# Sensor_Board.net
KiCad netlist of a schematic drawn in Altium Designer
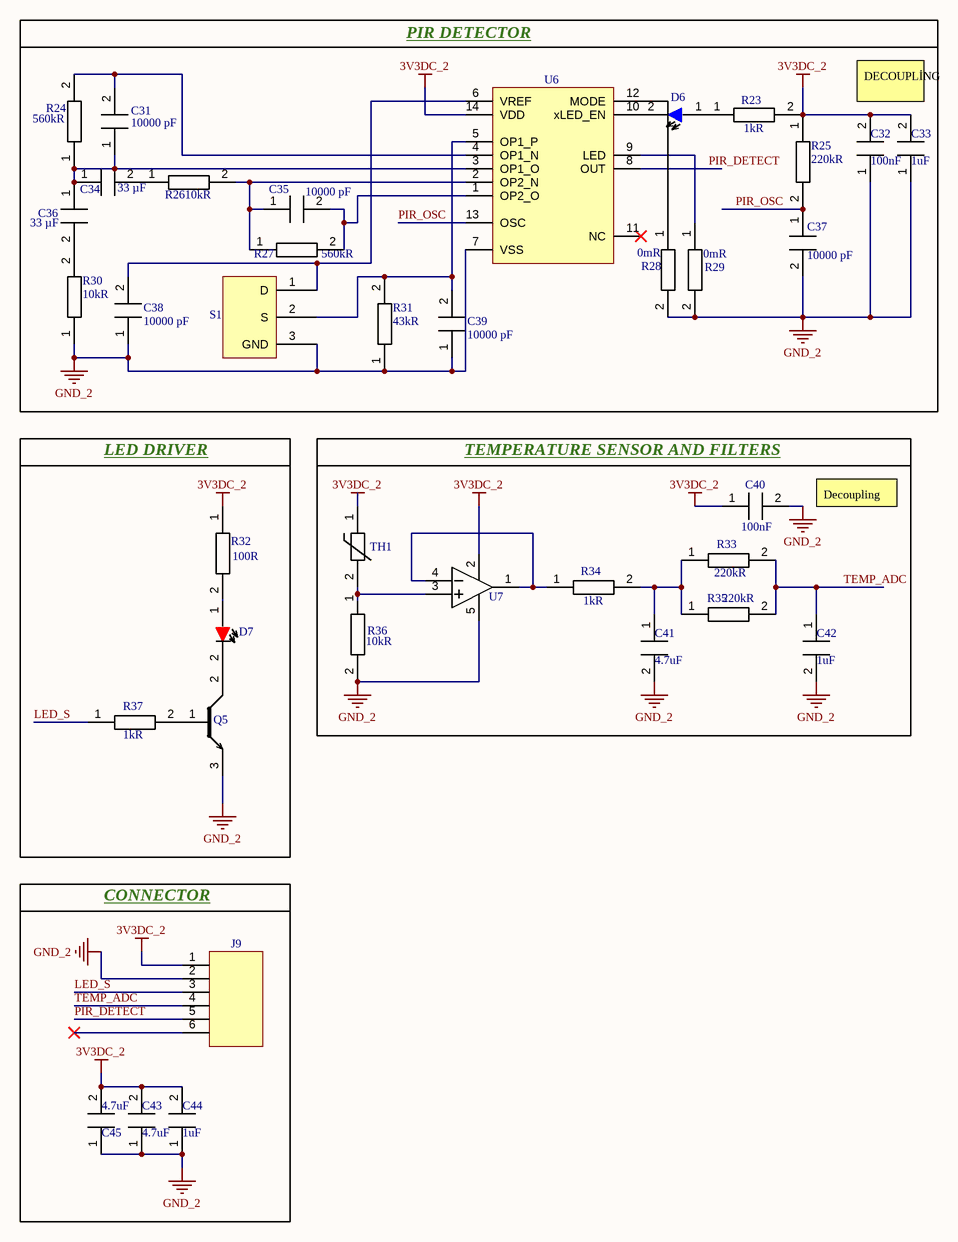
[diagram p0: Sensor_Board.SchDoc]

(export (version "E")
  (design (tool "Eeschema 10.0.6"))
  (components
    (comp (ref "C31")
      (value "10000 pF")
      (footprint "CAP_0603")
      (description "Multilayer Ceramic Capacitor, 0.01 F, 10%, X7R, 16 V, 0603 [1608 Metric] RoHS Compliant: Yes")
      (fields
        (field (name "MANUFACTURER") "Walsin Technologies")
        (field (name "MANUFACTURER PART NUMBER") "0603B103K160CT")
        (field (name "DESIGNED BY") "Ahmet Can")
      )
      (libsource (lib "AHMET_CAN_KARACAN") (part "CAP CER 10nF 0603"))
    )
    (comp (ref "C32")
      (value "CL21B104KBCNNNC")
      (footprint "CAP_0805")
      (description "Multilayer Ceramic Capacitor, 0.1 uF, 50 V, ± 10%, X7R, 0805 [2012 Metric]")
      (fields
        (field (name "MANUFACTURER") "Samsung")
        (field (name "TOLERANCE") "10%")
        (field (name "CAPACITANCE") "100nF")
      )
      (libsource (lib "AHMET_CAN_KARACAN") (part "CAP CER 100nF 0805"))
    )
    (comp (ref "C33")
      (value "1uF")
      (footprint "CAP_0805")
      (description "CAP CER %10 1uF 0805")
      (fields
        (field (name "MANUFACTURER") "Samsung")
        (field (name "MANUFACTURER PART NUMBER") "CL21B105KBFNNNE")
        (field (name "DESIGNED BY") "Ahmet Can")
      )
      (libsource (lib "AHMET_CAN_KARACAN") (part "CAP CER 1uF 0805"))
    )
    (comp (ref "C34")
      (value "33 µF")
      (footprint "CAP_1206")
      (description "Multilayer Ceramic Capacitor, 33 uF, 25 V, ± 20%, X5R, 1206 [3216 Metric]")
      (fields
        (field (name "MANUFACTURER") "TDK")
        (field (name "MANUFACTURER PART NUMBER") "C3216X5R1E336M160AC")
        (field (name "DESIGNED BY") "Ahmet Can")
      )
      (libsource (lib "AHMET_CAN_KARACAN") (part "CAP CER 33uF 1206"))
    )
    (comp (ref "C35")
      (value "10000 pF")
      (footprint "CAP_0603")
      (description "Multilayer Ceramic Capacitor, 0.01 F, 10%, X7R, 16 V, 0603 [1608 Metric] RoHS Compliant: Yes")
      (fields
        (field (name "MANUFACTURER") "Walsin Technologies")
        (field (name "MANUFACTURER PART NUMBER") "0603B103K160CT")
        (field (name "DESIGNED BY") "Ahmet Can")
      )
      (libsource (lib "AHMET_CAN_KARACAN") (part "CAP CER 10nF 0603"))
    )
    (comp (ref "C36")
      (value "33 µF")
      (footprint "CAP_1206")
      (description "Multilayer Ceramic Capacitor, 33 uF, 25 V, ± 20%, X5R, 1206 [3216 Metric]")
      (fields
        (field (name "MANUFACTURER") "TDK")
        (field (name "MANUFACTURER PART NUMBER") "C3216X5R1E336M160AC")
        (field (name "DESIGNED BY") "Ahmet Can")
      )
      (libsource (lib "AHMET_CAN_KARACAN") (part "CAP CER 33uF 1206"))
    )
    (comp (ref "C37")
      (value "10000 pF")
      (footprint "CAP_0603")
      (description "Multilayer Ceramic Capacitor, 0.01 F, 10%, X7R, 16 V, 0603 [1608 Metric] RoHS Compliant: Yes")
      (fields
        (field (name "MANUFACTURER") "Walsin Technologies")
        (field (name "MANUFACTURER PART NUMBER") "0603B103K160CT")
        (field (name "DESIGNED BY") "Ahmet Can")
      )
      (libsource (lib "AHMET_CAN_KARACAN") (part "CAP CER 10nF 0603"))
    )
    (comp (ref "C38")
      (value "10000 pF")
      (footprint "CAP_0603")
      (description "Multilayer Ceramic Capacitor, 0.01 F, 10%, X7R, 16 V, 0603 [1608 Metric] RoHS Compliant: Yes")
      (fields
        (field (name "MANUFACTURER") "Walsin Technologies")
        (field (name "MANUFACTURER PART NUMBER") "0603B103K160CT")
        (field (name "DESIGNED BY") "Ahmet Can")
      )
      (libsource (lib "AHMET_CAN_KARACAN") (part "CAP CER 10nF 0603"))
    )
    (comp (ref "C39")
      (value "10000 pF")
      (footprint "CAP_0603")
      (description "Multilayer Ceramic Capacitor, 0.01 F, 10%, X7R, 16 V, 0603 [1608 Metric] RoHS Compliant: Yes")
      (fields
        (field (name "MANUFACTURER") "Walsin Technologies")
        (field (name "MANUFACTURER PART NUMBER") "0603B103K160CT")
        (field (name "DESIGNED BY") "Ahmet Can")
      )
      (libsource (lib "AHMET_CAN_KARACAN") (part "CAP CER 10nF 0603"))
    )
    (comp (ref "C40")
      (value "CL21B104KBCNNNC")
      (footprint "CAP_0805")
      (description "Multilayer Ceramic Capacitor, 0.1 uF, 50 V, ± 10%, X7R, 0805 [2012 Metric]")
      (fields
        (field (name "MANUFACTURER") "Samsung")
        (field (name "TOLERANCE") "10%")
        (field (name "CAPACITANCE") "100nF")
      )
      (libsource (lib "AHMET_CAN_KARACAN") (part "CAP CER 100nF 0805"))
    )
    (comp (ref "C41")
      (value "4.7uF")
      (footprint "CAP_0805")
      (description "Multilayer Ceramic Capacitor, 4.7 uF, 25 V, ± 10%, X5R, 0805 [2012 Metric]")
      (fields
        (field (name "MANUFACTURER") "Samsung")
        (field (name "MANUFACTURER PART NUMBER") "CL21A475KAQNNNE")
        (field (name "DESIGNED BY") "Ahmet Can")
      )
      (libsource (lib "AHMET_CAN_KARACAN") (part "CAP CER 4.7uF 0805"))
    )
    (comp (ref "C42")
      (value "1uF")
      (footprint "CAP_0805")
      (description "CAP CER %10 1uF 0805")
      (fields
        (field (name "MANUFACTURER") "Samsung")
        (field (name "MANUFACTURER PART NUMBER") "CL21B105KBFNNNE")
      )
      (libsource (lib "AHMET_CAN_KARACAN") (part "CAP CER 1uF 0805"))
    )
    (comp (ref "C43")
      (value "4.7uF")
      (footprint "CAP_0805")
      (description "Multilayer Ceramic Capacitor, 4.7 uF, 25 V, ± 10%, X5R, 0805 [2012 Metric]")
      (fields
        (field (name "MANUFACTURER") "Samsung")
        (field (name "MANUFACTURER PART NUMBER") "CL21A475KAQNNNE")
        (field (name "DESIGNED BY") "Ahmet Can")
      )
      (libsource (lib "AHMET_CAN_KARACAN") (part "CAP CER 4.7uF 0805"))
    )
    (comp (ref "C44")
      (value "1uF")
      (footprint "CAP_0805")
      (description "CAP CER %10 1uF 0805")
      (fields
        (field (name "MANUFACTURER") "Samsung")
        (field (name "MANUFACTURER PART NUMBER") "CL21B105KBFNNNE")
        (field (name "DESIGNED BY") "Ahmet Can")
      )
      (libsource (lib "AHMET_CAN_KARACAN") (part "CAP CER 1uF 0805"))
    )
    (comp (ref "C45")
      (value "4.7uF")
      (footprint "CAP_0805")
      (description "Multilayer Ceramic Capacitor, 4.7 uF, 25 V, ± 10%, X5R, 0805 [2012 Metric]")
      (fields
        (field (name "MANUFACTURER") "Samsung")
        (field (name "MANUFACTURER PART NUMBER") "CL21A475KAQNNNE")
        (field (name "DESIGNED BY") "Ahmet Can")
      )
      (libsource (lib "AHMET_CAN_KARACAN") (part "CAP CER 4.7uF 0805"))
    )
    (comp (ref "D6")
      (value "0805BBD8100S01")
      (footprint "LED_BLUE_0805")
      (description "Blue 467nm LED Indication - Discrete 2.6V 0805 (2012 Metric)")
      (fields (field (name "MANUFACTURER") "BNDLIGHT") (field (name "DESIGNED BY") "Ahmet Can"))
      (libsource (lib "AHMET_CAN_KARACAN") (part "LED_BLUE 0805"))
    )
    (comp (ref "D7")
      (value "HSMC-C170")
      (footprint "LED_RED_0805")
      (description "Red 626nm LED Indication - Discrete 1.9V 0805 (2012 Metric)")
      (fields (field (name "MANUFACTURER") "Broadcom Avago") (field (name "DESIGNED BY") "Ahmet Can"))
      (libsource (lib "AHMET_CAN_KARACAN") (part "LED_RED 0805"))
    )
    (comp (ref "J9")
      (value "64800611622")
      (footprint "6 HOLE CONNECTOR")
      (description "WR-WTB Wire-to-Board Connectors 1.50 mm")
      (fields (field (name "MANUFACTURER") "Wurth Electronics") (field (name "DESIGNED BY") "Ahmet Can"))
      (libsource (lib "AHMET_CAN_KARACAN") (part "J_64800611622"))
    )
    (comp (ref "Q5")
      (value "MMBT3904-7-F")
      (footprint "SOT_23_3")
      (description "Transistor General Purpose BJT NPN 40 Volt 0.2A Automotive 3-Pin SOT-23-3")
      (fields (field (name "MANUFACTURER") "Diodes Zetex") (field (name "DESIGNED BY") "Ahmet Can"))
      (libsource (lib "AHMET_CAN_KARACAN") (part "Q_MMBT3904-7-F"))
    )
    (comp (ref "R23")
      (value "1kR")
      (footprint "RE_0603")
      (description "SMD Chip Resistor, 1 kOhm, ± 1%, 63 mW, 0402 [1005 Metric], Thick Film, General Purpose")
      (fields
        (field (name "MANUFACTURER") "Yageo")
        (field (name "MANUFACTURER PART NUMBER") "RC0402FR-071KL")
        (field (name "DESIGNED BY") "Ahmet Can")
      )
      (libsource (lib "AHMET_CAN_KARACAN") (part "RES 1K 0603"))
    )
    (comp (ref "R24")
      (value "560kR")
      (footprint "RE_0603")
      (description "SMD Chip Resistor, 560 kOhm, ± 5%, 100 mW, 0603 [1608 Metric], Thick Film, General Purpose")
      (fields
        (field (name "MANUFACTURER") "Yageo")
        (field (name "MANUFACTURER PART NUMBER") "RC0603JR-07560KL")
        (field (name "DESIGNED BY") "Ahmet Can")
      )
      (libsource (lib "AHMET_CAN_KARACAN") (part "RES 560K 0603"))
    )
    (comp (ref "R25")
      (value "220kR")
      (footprint "RE_0603")
      (description "SMD Chip Resistor, 220 kOhm, ± 5%, 100 mW, 0603 [1608 Metric], Thick Film, General Purpose")
      (fields
        (field (name "MANUFACTURER") "Yageo")
        (field (name "MANUFACTURER PART NUMBER") "RC0603JR-07220KL")
        (field (name "DESIGNED BY") "Ahmet Can")
      )
      (libsource (lib "AHMET_CAN_KARACAN") (part "RES 220K 0603"))
    )
    (comp (ref "R26")
      (value "10kR")
      (footprint "RE_0402")
      (description "SMD Chip Resistor, 10 kOhm, ± 5%, 63 mW, 0402 [1005 Metric], Thick Film, General Purpose")
      (fields
        (field (name "MANUFACTURER") "Yageo")
        (field (name "MANUFACTURER PART NUMBER") "RC0402JR-0710KL")
        (field (name "DESIGNED BY") "Ahmet Can")
      )
      (libsource (lib "AHMET_CAN_KARACAN") (part "RES 10K 0402"))
    )
    (comp (ref "R27")
      (value "560kR")
      (footprint "RE_0603")
      (description "SMD Chip Resistor, 560 kOhm, ± 5%, 100 mW, 0603 [1608 Metric], Thick Film, General Purpose")
      (fields
        (field (name "MANUFACTURER") "Yageo")
        (field (name "MANUFACTURER PART NUMBER") "RC0603JR-07560KL")
        (field (name "DESIGNED BY") "Ahmet Can")
      )
      (libsource (lib "AHMET_CAN_KARACAN") (part "RES 560K 0603"))
    )
    (comp (ref "R28")
      (value "0mR")
      (footprint "RE_0603")
      (description "Zero Ohm Resistor, Jumper, 0603 [1608 Metric], Thick Film, 100 mW, 1 A, Surface Mount")
      (fields
        (field (name "MANUFACTURER") "Yageo")
        (field (name "MANUFACTURER PART NUMBER") "RC0603JR-070RL")
        (field (name "DESIGNED BY") "Ahmet Can")
      )
      (libsource (lib "AHMET_CAN_KARACAN") (part "RES 0K 0603"))
    )
    (comp (ref "R29")
      (value "0mR")
      (footprint "RE_0603")
      (description "Zero Ohm Resistor, Jumper, 0603 [1608 Metric], Thick Film, 100 mW, 1 A, Surface Mount")
      (fields
        (field (name "MANUFACTURER") "Yageo")
        (field (name "MANUFACTURER PART NUMBER") "RC0603JR-070RL")
        (field (name "DESIGNED BY") "Ahmet Can")
      )
      (libsource (lib "AHMET_CAN_KARACAN") (part "RES 0K 0603"))
    )
    (comp (ref "R30")
      (value "10kR")
      (footprint "RE_0402")
      (description "SMD Chip Resistor, 10 kOhm, ± 5%, 63 mW, 0402 [1005 Metric], Thick Film, General Purpose")
      (fields
        (field (name "MANUFACTURER") "Yageo")
        (field (name "MANUFACTURER PART NUMBER") "RC0402JR-0710KL")
        (field (name "DESIGNED BY") "Ahmet Can")
      )
      (libsource (lib "AHMET_CAN_KARACAN") (part "RES 10K 0402"))
    )
    (comp (ref "R31")
      (value "43kR")
      (footprint "RE_0603")
      (description "Res Thick Film 0603 43K Ohm 5% 0.1W(1/10W) ±100ppm/°C Pad SMD T/R")
      (fields
        (field (name "MANUFACTURER") "Yageo")
        (field (name "MANUFACTURER PART NUMBER") "RC0603JR-0743KL")
        (field (name "DESIGNED BY") "Ahmet Can")
      )
      (libsource (lib "AHMET_CAN_KARACAN") (part "RES 43K 0603"))
    )
    (comp (ref "R32")
      (value "100R")
      (footprint "RE_0603")
      (description "Res Thick Film 0603 100 Ohm 5% 1/10W ±100ppm/°C Molded SMD SMD Paper T/R")
      (fields
        (field (name "MANUFACTURER") "Yageo")
        (field (name "MANUFACTURER PART NUMBER") "RC0603JR-07100RL")
        (field (name "DESIGNED BY") "Ahmet Can")
      )
      (libsource (lib "AHMET_CAN_KARACAN") (part "RES 100 0603"))
    )
    (comp (ref "R33")
      (value "220kR")
      (footprint "RE_0603")
      (description "SMD Chip Resistor, 220 kOhm, ± 5%, 100 mW, 0603 [1608 Metric], Thick Film, General Purpose")
      (fields
        (field (name "MANUFACTURER") "Yageo")
        (field (name "MANUFACTURER PART NUMBER") "RC0603JR-07220KL")
        (field (name "DESIGNED BY") "Ahmet Can")
      )
      (libsource (lib "AHMET_CAN_KARACAN") (part "RES 220K 0603"))
    )
    (comp (ref "R34")
      (value "1kR")
      (footprint "RE_0603")
      (description "SMD Chip Resistor, 1 kOhm, ± 1%, 63 mW, 0402 [1005 Metric], Thick Film, General Purpose")
      (fields
        (field (name "MANUFACTURER") "Yageo")
        (field (name "MANUFACTURER PART NUMBER") "RC0402FR-071KL")
        (field (name "DESIGNED BY") "Ahmet Can")
      )
      (libsource (lib "AHMET_CAN_KARACAN") (part "RES 1K 0603"))
    )
    (comp (ref "R35")
      (value "220kR")
      (footprint "RE_0603")
      (description "SMD Chip Resistor, 220 kOhm, ± 5%, 100 mW, 0603 [1608 Metric], Thick Film, General Purpose")
      (fields
        (field (name "MANUFACTURER") "Yageo")
        (field (name "MANUFACTURER PART NUMBER") "RC0603JR-07220KL")
        (field (name "DESIGNED BY") "Ahmet Can")
      )
      (libsource (lib "AHMET_CAN_KARACAN") (part "RES 220K 0603"))
    )
    (comp (ref "R36")
      (value "10kR")
      (footprint "RE_0402")
      (description "SMD Chip Resistor, 10 kOhm, ± 5%, 63 mW, 0402 [1005 Metric], Thick Film, General Purpose")
      (fields
        (field (name "MANUFACTURER") "Yageo")
        (field (name "MANUFACTURER PART NUMBER") "RC0402JR-0710KL")
        (field (name "DESIGNED BY") "Ahmet Can")
      )
      (libsource (lib "AHMET_CAN_KARACAN") (part "RES 10K 0402"))
    )
    (comp (ref "R37")
      (value "1kR")
      (footprint "RE_0603")
      (description "SMD Chip Resistor, 1 kOhm, ± 1%, 63 mW, 0402 [1005 Metric], Thick Film, General Purpose")
      (fields
        (field (name "MANUFACTURER") "Yageo")
        (field (name "MANUFACTURER PART NUMBER") "RC0402FR-071KL")
        (field (name "DESIGNED BY") "Ahmet Can")
      )
      (libsource (lib "AHMET_CAN_KARACAN") (part "RES 1K 0603"))
    )
    (comp (ref "S1")
      (value "LHI 878/3902")
      (footprint "LHI 878/3902")
      (description "Sensor PIR (Passive Infrared) TO-205AA, TO-5-3 Metal Can")
      (fields (field (name "MANUFACTURER") "Excelitas Technologies") (field (name "DESIGNED BY") "Ahmet Can"))
      (libsource (lib "AHMET_CAN_KARACAN") (part "PIR_LHI 878/3902"))
    )
    (comp (ref "TH1")
      (value "TFPT1206L1002FM")
      (footprint "RE_1206")
      (description "Thermistor PTC 10K Ohm 1% 2-Pin 1206 Surface Mount Solder Pad T/R Automotive")
      (fields
        (field (name "MANUFACTURER") "Vishay Dale")
        (field (name "TOLERANCE") "1%")
        (field (name "DESIGNED BY") "Ahmet Can")
      )
      (libsource (lib "AHMET_CAN_KARACAN") (part "TH_TFPT1206L1002FM"))
    )
    (comp (ref "U6")
      (value "NCS36000DRG")
      (footprint "14_SOIC")
      (description "NCS36000 Series Single 5.75V Passive Infrared Detector Controller (PIR) -SOIC-14")
      (fields (field (name "MANUFACTURER") "ON Semiconductor") (field (name "DESIGNED BY") "Ahmet Can"))
      (libsource (lib "AHMET_CAN_KARACAN") (part "U_PIR_NCS36000DRG"))
    )
    (comp (ref "U7")
      (value "OPA314AIDBVR")
      (footprint "SOT_23_5")
      (description "IC OPAMP GP 3MHZ RRO SOT23-5")
      (fields (field (name "MANUFACTURER") "Texas Instruments") (field (name "DESIGNED BY") "Ahmet Can"))
      (libsource (lib "AHMET_CAN_KARACAN") (part "U_OPA314AIDBVR"))
    )
  )
  (nets
    (net (code "1") (name "/LED_S") (class "Default")
      (node (ref "J9") (pin "3") (pintype "passive"))
      (node (ref "R37") (pin "1") (pintype "passive"))
    )
    (net (code "2") (name "/PIR_DETECT") (class "Default")
      (node (ref "J9") (pin "5") (pintype "passive"))
      (node (ref "U6") (pin "8") (pinfunction "OUT_8") (pintype "passive"))
    )
    (net (code "3") (name "/PIR_OSC") (class "Default")
      (node (ref "C37") (pin "1") (pintype "passive"))
      (node (ref "R25") (pin "2") (pintype "passive"))
      (node (ref "U6") (pin "13") (pinfunction "OSC_13") (pintype "passive"))
    )
    (net (code "4") (name "/TEMP_ADC") (class "Default")
      (node (ref "C42") (pin "1") (pintype "passive"))
      (node (ref "J9") (pin "4") (pintype "passive"))
      (node (ref "R33") (pin "2") (pintype "passive"))
      (node (ref "R35") (pin "2") (pintype "passive"))
    )
    (net (code "5") (name "3V3DC_2") (class "Default")
      (node (ref "C32") (pin "2") (pintype "passive"))
      (node (ref "C33") (pin "2") (pintype "passive"))
      (node (ref "C40") (pin "1") (pintype "passive"))
      (node (ref "C43") (pin "2") (pintype "passive"))
      (node (ref "C44") (pin "2") (pintype "passive"))
      (node (ref "C45") (pin "2") (pintype "passive"))
      (node (ref "J9") (pin "1") (pintype "passive"))
      (node (ref "R23") (pin "2") (pintype "passive"))
      (node (ref "R25") (pin "1") (pintype "passive"))
      (node (ref "R32") (pin "1") (pintype "passive"))
      (node (ref "TH1") (pin "1") (pintype "passive"))
      (node (ref "U6") (pin "14") (pinfunction "VDD_14") (pintype "passive"))
      (node (ref "U7") (pin "2") (pinfunction "V-_2") (pintype "passive"))
    )
    (net (code "6") (name "GND_2") (class "Default")
      (node (ref "C32") (pin "1") (pintype "passive"))
      (node (ref "C33") (pin "1") (pintype "passive"))
      (node (ref "C37") (pin "2") (pintype "passive"))
      (node (ref "C38") (pin "1") (pintype "passive"))
      (node (ref "C39") (pin "1") (pintype "passive"))
      (node (ref "C40") (pin "2") (pintype "passive"))
      (node (ref "C41") (pin "2") (pintype "passive"))
      (node (ref "C42") (pin "2") (pintype "passive"))
      (node (ref "C43") (pin "1") (pintype "passive"))
      (node (ref "C44") (pin "1") (pintype "passive"))
      (node (ref "C45") (pin "1") (pintype "passive"))
      (node (ref "J9") (pin "2") (pintype "passive"))
      (node (ref "Q5") (pin "3") (pintype "passive"))
      (node (ref "R28") (pin "2") (pintype "passive"))
      (node (ref "R29") (pin "2") (pintype "passive"))
      (node (ref "R30") (pin "1") (pintype "passive"))
      (node (ref "R31") (pin "1") (pintype "passive"))
      (node (ref "R36") (pin "2") (pintype "passive"))
      (node (ref "S1") (pin "3") (pinfunction "GND_3") (pintype "passive"))
      (node (ref "U6") (pin "7") (pinfunction "VSS_7") (pintype "passive"))
      (node (ref "U7") (pin "5") (pinfunction "V+_5") (pintype "passive"))
    )
    (net (code "7") (name "Net-(C34-Pad2)") (class "Default")
      (node (ref "C34") (pin "2") (pintype "passive"))
      (node (ref "R26") (pin "1") (pintype "passive"))
    )
    (net (code "8") (name "Net-(C36-Pad2)") (class "Default")
      (node (ref "C36") (pin "2") (pintype "passive"))
      (node (ref "R30") (pin "2") (pintype "passive"))
    )
    (net (code "9") (name "Net-(C41-Pad1)") (class "Default")
      (node (ref "C41") (pin "1") (pintype "passive"))
      (node (ref "R33") (pin "1") (pintype "passive"))
      (node (ref "R34") (pin "2") (pintype "passive"))
      (node (ref "R35") (pin "1") (pintype "passive"))
    )
    (net (code "10") (name "Net-(D6-Pad1)") (class "Default")
      (node (ref "D6") (pin "1") (pintype "passive"))
      (node (ref "R23") (pin "1") (pintype "passive"))
    )
    (net (code "11") (name "Net-(D7-Pad1)") (class "Default")
      (node (ref "D7") (pin "1") (pintype "passive"))
      (node (ref "R32") (pin "2") (pintype "passive"))
    )
    (net (code "12") (name "Net-(D7-Pad2)") (class "Default")
      (node (ref "D7") (pin "2") (pintype "passive"))
      (node (ref "Q5") (pin "2") (pintype "passive"))
    )
    (net (code "13") (name "Net-(Q5-Pad1)") (class "Default")
      (node (ref "Q5") (pin "1") (pintype "passive"))
      (node (ref "R37") (pin "2") (pintype "passive"))
    )
    (net (code "14") (name "Net-(S1-D)") (class "Default")
      (node (ref "C38") (pin "2") (pintype "passive"))
      (node (ref "S1") (pin "1") (pinfunction "D_1") (pintype "passive"))
      (node (ref "U6") (pin "6") (pinfunction "VREF_6") (pintype "passive"))
    )
    (net (code "15") (name "Net-(S1-S)") (class "Default")
      (node (ref "C39") (pin "2") (pintype "passive"))
      (node (ref "R31") (pin "2") (pintype "passive"))
      (node (ref "S1") (pin "2") (pinfunction "S_2") (pintype "passive"))
      (node (ref "U6") (pin "5") (pinfunction "OP1_P_5") (pintype "passive"))
    )
    (net (code "16") (name "Net-(U6-LED)") (class "Default")
      (node (ref "R29") (pin "1") (pintype "passive"))
      (node (ref "U6") (pin "9") (pinfunction "LED_9") (pintype "passive"))
    )
    (net (code "17") (name "Net-(U6-MODE)") (class "Default")
      (node (ref "R28") (pin "1") (pintype "passive"))
      (node (ref "U6") (pin "12") (pinfunction "MODE_12") (pintype "passive"))
    )
    (net (code "18") (name "Net-(U6-OP1_N)") (class "Default")
      (node (ref "C31") (pin "2") (pintype "passive"))
      (node (ref "R24") (pin "2") (pintype "passive"))
      (node (ref "U6") (pin "4") (pinfunction "OP1_N_4") (pintype "passive"))
    )
    (net (code "19") (name "Net-(U6-OP1_O)") (class "Default")
      (node (ref "C31") (pin "1") (pintype "passive"))
      (node (ref "C34") (pin "1") (pintype "passive"))
      (node (ref "C36") (pin "1") (pintype "passive"))
      (node (ref "R24") (pin "1") (pintype "passive"))
      (node (ref "U6") (pin "3") (pinfunction "OP1_O_3") (pintype "passive"))
    )
    (net (code "20") (name "Net-(U6-OP2_N)") (class "Default")
      (node (ref "C35") (pin "1") (pintype "passive"))
      (node (ref "R26") (pin "2") (pintype "passive"))
      (node (ref "R27") (pin "1") (pintype "passive"))
      (node (ref "U6") (pin "2") (pinfunction "OP2_N_2") (pintype "passive"))
    )
    (net (code "21") (name "Net-(U6-OP2_O)") (class "Default")
      (node (ref "C35") (pin "2") (pintype "passive"))
      (node (ref "R27") (pin "2") (pintype "passive"))
      (node (ref "U6") (pin "1") (pinfunction "OP2_O_1") (pintype "passive"))
    )
    (net (code "22") (name "Net-(U6-xLED_EN)") (class "Default")
      (node (ref "D6") (pin "2") (pintype "passive"))
      (node (ref "U6") (pin "10") (pinfunction "xLED_EN_10") (pintype "passive"))
    )
    (net (code "23") (name "Net-(U7-+IN)") (class "Default")
      (node (ref "R36") (pin "1") (pintype "passive"))
      (node (ref "TH1") (pin "2") (pintype "passive"))
      (node (ref "U7") (pin "3") (pinfunction "+IN_3") (pintype "passive"))
    )
    (net (code "24") (name "Net-(U7--IN)") (class "Default")
      (node (ref "R34") (pin "1") (pintype "passive"))
      (node (ref "U7") (pin "1") (pinfunction "OUT_1") (pintype "passive"))
      (node (ref "U7") (pin "4") (pinfunction "-IN_4") (pintype "passive"))
    )
    (net (code "25") (name "unconnected-(J9-Pad6)") (class "Default")
      (node (ref "J9") (pin "6") (pintype "passive+no_connect"))
    )
    (net (code "26") (name "unconnected-(U6-NC-Pad11)") (class "Default")
      (node (ref "U6") (pin "11") (pinfunction "NC_11") (pintype "passive+no_connect"))
    )
  )
)
